# airmachine.net
KiCad netlist of a schematic drawn in Altium Designer
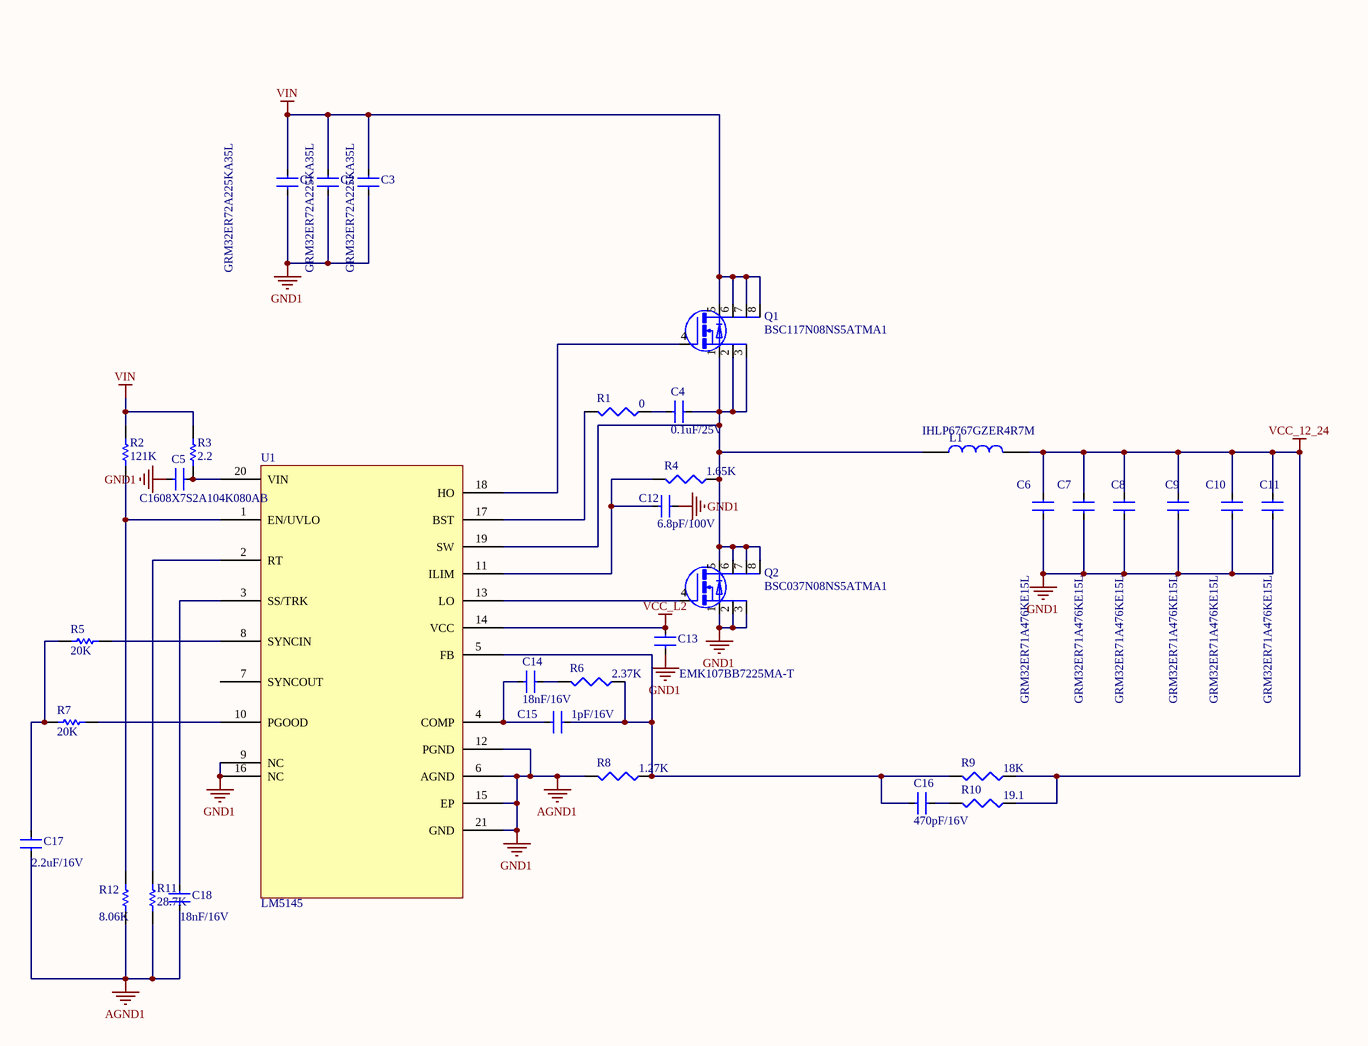
[diagram p0: airmachine.SchDoc]

(export (version "E")
  (design (tool "Eeschema 10.0.6"))
  (components
    (comp (ref "C1")
      (value "GRM32ER72A225KA35L")
      (footprint "1210C")
      (description "CCX85-103")
      (libsource (lib "无极性电容") (part "0.01UF"))
    )
    (comp (ref "C2")
      (value "GRM32ER72A225KA35L")
      (footprint "1210C")
      (description "CCX85-103")
      (libsource (lib "无极性电容") (part "0.01UF"))
    )
    (comp (ref "C3")
      (value "GRM32ER72A225KA35L")
      (footprint "1210C")
      (description "CCX85-103")
      (libsource (lib "无极性电容") (part "0.01UF"))
    )
    (comp (ref "C4")
      (value "0.1uF/25V")
      (footprint "0603C")
      (description "CCX85-103")
      (libsource (lib "无极性电容") (part "0.01UF"))
    )
    (comp (ref "C5")
      (value "C1608X7S2A104K080AB")
      (footprint "0603C")
      (description "CCX85-103")
      (libsource (lib "无极性电容") (part "0.01UF"))
    )
    (comp (ref "C6")
      (value "GRM32ER71A476KE15L")
      (footprint "1210C")
      (description "CCX85-103")
      (libsource (lib "无极性电容") (part "0.01UF"))
    )
    (comp (ref "C7")
      (value "GRM32ER71A476KE15L")
      (footprint "1210C")
      (description "CCX85-103")
      (libsource (lib "无极性电容") (part "0.01UF"))
    )
    (comp (ref "C8")
      (value "GRM32ER71A476KE15L")
      (footprint "1210C")
      (description "CCX85-103")
      (libsource (lib "无极性电容") (part "0.01UF"))
    )
    (comp (ref "C9")
      (value "GRM32ER71A476KE15L")
      (footprint "1210C")
      (description "CCX85-103")
      (libsource (lib "无极性电容") (part "0.01UF"))
    )
    (comp (ref "C10")
      (value "GRM32ER71A476KE15L")
      (footprint "1210C")
      (description "CCX85-103")
      (libsource (lib "无极性电容") (part "0.01UF"))
    )
    (comp (ref "C11")
      (value "GRM32ER71A476KE15L")
      (footprint "1210C")
      (description "CCX85-103")
      (libsource (lib "无极性电容") (part "0.01UF"))
    )
    (comp (ref "C12")
      (value "6.8pF/100V")
      (footprint "0603C")
      (description "CCX85-103")
      (libsource (lib "无极性电容") (part "0.01UF"))
    )
    (comp (ref "C13")
      (value "EMK107BB7225MA-T")
      (footprint "0603C")
      (description "CCX85-103")
      (libsource (lib "无极性电容") (part "0.01UF"))
    )
    (comp (ref "C14")
      (value "18nF/16V")
      (footprint "0603C")
      (description "CCX85-103")
      (libsource (lib "无极性电容") (part "0.01UF"))
    )
    (comp (ref "C15")
      (value "1pF/16V")
      (footprint "0603C")
      (description "CCX85-103")
      (libsource (lib "无极性电容") (part "0.01UF"))
    )
    (comp (ref "C16")
      (value "470pF/16V")
      (footprint "0603C")
      (description "CCX85-103")
      (libsource (lib "无极性电容") (part "0.01UF"))
    )
    (comp (ref "C17")
      (value "2.2uF/16V")
      (footprint "0603C")
      (description "CCX85-103")
      (libsource (lib "无极性电容") (part "0.01UF"))
    )
    (comp (ref "C18")
      (value "18nF/16V")
      (footprint "0603C")
      (description "CCX85-103")
      (libsource (lib "无极性电容") (part "0.01UF"))
    )
    (comp (ref "L1")
      (value "IHLP6767GZER4R7M")
      (footprint "IHLP-6767GZ")
      (libsource (lib "*") (part "INDUCTOR"))
    )
    (comp (ref "Q1")
      (value "BSC117N08NS5ATMA1")
      (footprint "PowerPAK SO-8")
      (description "Si4004DY")
      (libsource (lib "Schlib_20110825") (part "Si4004DY"))
    )
    (comp (ref "Q2")
      (value "BSC037N08NS5ATMA1")
      (footprint "PowerPAK SO-8")
      (description "Si4004DY")
      (libsource (lib "Schlib_20110825") (part "Si4004DY"))
    )
    (comp (ref "R1")
      (value "0")
      (footprint "0603R")
      (description "Resistor")
      (fields (field (name "PUBLISHER") "Altium Limited"))
      (libsource (lib "SM") (part "Res3"))
    )
    (comp (ref "R2")
      (value "121K")
      (footprint "0805R")
      (description "Semiconductor Resistor")
      (fields (field (name "PUBLISHER") "Altium Limited"))
      (libsource (lib "Miscellaneous Devices") (part "Res Semi"))
    )
    (comp (ref "R3")
      (value "2.2")
      (footprint "0603R")
      (description "Semiconductor Resistor")
      (fields (field (name "PUBLISHER") "Altium Limited"))
      (libsource (lib "Miscellaneous Devices") (part "Res Semi"))
    )
    (comp (ref "R4")
      (value "1.65K")
      (footprint "0603R")
      (description "Resistor")
      (fields (field (name "PUBLISHER") "Altium Limited"))
      (libsource (lib "SM") (part "Res3"))
    )
    (comp (ref "R5")
      (value "20K")
      (footprint "0603R")
      (description "Semiconductor Resistor")
      (fields (field (name "PUBLISHER") "Altium Limited"))
      (libsource (lib "Miscellaneous Devices") (part "Res Semi"))
    )
    (comp (ref "R6")
      (value "2.37K")
      (footprint "0603R")
      (description "Resistor")
      (fields (field (name "PUBLISHER") "Altium Limited"))
      (libsource (lib "SM") (part "Res3"))
    )
    (comp (ref "R7")
      (value "20K")
      (footprint "0603R")
      (description "Semiconductor Resistor")
      (fields (field (name "PUBLISHER") "Altium Limited"))
      (libsource (lib "Miscellaneous Devices") (part "Res Semi"))
    )
    (comp (ref "R8")
      (value "1.27K")
      (footprint "0603R")
      (description "Resistor")
      (fields (field (name "PUBLISHER") "Altium Limited"))
      (libsource (lib "SM") (part "Res3"))
    )
    (comp (ref "R9")
      (value "18K")
      (footprint "0603R")
      (description "Resistor")
      (fields (field (name "PUBLISHER") "Altium Limited"))
      (libsource (lib "SM") (part "Res3"))
    )
    (comp (ref "R10")
      (value "19.1")
      (footprint "0603R")
      (description "Resistor")
      (fields (field (name "PUBLISHER") "Altium Limited"))
      (libsource (lib "SM") (part "Res3"))
    )
    (comp (ref "R11")
      (value "28.7K")
      (footprint "0603R")
      (description "Semiconductor Resistor")
      (fields (field (name "PUBLISHER") "Altium Limited"))
      (libsource (lib "Miscellaneous Devices") (part "Res Semi"))
    )
    (comp (ref "R12")
      (value "8.06K")
      (footprint "0603R")
      (description "Semiconductor Resistor")
      (fields (field (name "PUBLISHER") "Altium Limited"))
      (libsource (lib "Miscellaneous Devices") (part "Res Semi"))
    )
    (comp (ref "U1")
      (value "LM5145")
      (footprint "QFN050P600-8N")
      (libsource (lib "Schlib_20110825") (part "LM5145"))
    )
  )
  (nets
    (net (code "1") (name "AGND1") (class "Default")
      (node (ref "C1") (pin "2") (pinfunction "2_2") (pintype "passive"))
      (node (ref "C10") (pin "2") (pinfunction "2_2") (pintype "passive"))
      (node (ref "C11") (pin "2") (pinfunction "2_2") (pintype "passive"))
      (node (ref "C12") (pin "1") (pinfunction "1_1") (pintype "passive"))
      (node (ref "C13") (pin "2") (pinfunction "2_2") (pintype "passive"))
      (node (ref "C17") (pin "2") (pinfunction "2_2") (pintype "passive"))
      (node (ref "C18") (pin "2") (pinfunction "2_2") (pintype "passive"))
      (node (ref "C2") (pin "2") (pinfunction "2_2") (pintype "passive"))
      (node (ref "C3") (pin "2") (pinfunction "2_2") (pintype "passive"))
      (node (ref "C5") (pin "1") (pinfunction "1_1") (pintype "passive"))
      (node (ref "C6") (pin "2") (pinfunction "2_2") (pintype "passive"))
      (node (ref "C7") (pin "2") (pinfunction "2_2") (pintype "passive"))
      (node (ref "C8") (pin "2") (pinfunction "2_2") (pintype "passive"))
      (node (ref "C9") (pin "2") (pinfunction "2_2") (pintype "passive"))
      (node (ref "Q2") (pin "1") (pinfunction "S_1") (pintype "passive"))
      (node (ref "Q2") (pin "2") (pinfunction "S_2") (pintype "passive"))
      (node (ref "Q2") (pin "3") (pinfunction "S_3") (pintype "passive"))
      (node (ref "R11") (pin "1") (pinfunction "1_1") (pintype "passive"))
      (node (ref "R12") (pin "1") (pinfunction "1_1") (pintype "passive"))
      (node (ref "R8") (pin "2") (pinfunction "2_2") (pintype "passive"))
      (node (ref "U1") (pin "12") (pinfunction "PGND_12") (pintype "passive"))
      (node (ref "U1") (pin "15") (pinfunction "EP_15") (pintype "passive"))
      (node (ref "U1") (pin "16") (pinfunction "NC_16") (pintype "passive"))
      (node (ref "U1") (pin "21") (pinfunction "GND_21") (pintype "passive"))
      (node (ref "U1") (pin "6") (pinfunction "AGND_6") (pintype "passive"))
      (node (ref "U1") (pin "9") (pinfunction "NC_9") (pintype "passive"))
    )
    (net (code "2") (name "Net-(C4-Pad1)") (class "Default")
      (node (ref "C4") (pin "1") (pinfunction "1_1") (pintype "passive"))
      (node (ref "R1") (pin "1") (pinfunction "1_1") (pintype "passive"))
    )
    (net (code "3") (name "Net-(C14-Pad2)") (class "Default")
      (node (ref "C14") (pin "2") (pinfunction "2_2") (pintype "passive"))
      (node (ref "R6") (pin "2") (pinfunction "2_2") (pintype "passive"))
    )
    (net (code "4") (name "Net-(C16-Pad2)") (class "Default")
      (node (ref "C16") (pin "2") (pinfunction "2_2") (pintype "passive"))
      (node (ref "R10") (pin "2") (pinfunction "2_2") (pintype "passive"))
    )
    (net (code "5") (name "Net-(C17-Pad1)") (class "Default")
      (node (ref "C17") (pin "1") (pinfunction "1_1") (pintype "passive"))
      (node (ref "R5") (pin "2") (pinfunction "2_2") (pintype "passive"))
      (node (ref "R7") (pin "2") (pinfunction "2_2") (pintype "passive"))
    )
    (net (code "6") (name "Net-(Q1-G)") (class "Default")
      (node (ref "Q1") (pin "4") (pinfunction "G_4") (pintype "passive"))
      (node (ref "U1") (pin "18") (pinfunction "HO_18") (pintype "passive"))
    )
    (net (code "7") (name "Net-(Q2-G)") (class "Default")
      (node (ref "Q2") (pin "4") (pinfunction "G_4") (pintype "passive"))
      (node (ref "U1") (pin "13") (pinfunction "LO_13") (pintype "passive"))
    )
    (net (code "8") (name "Net-(U1-BST)") (class "Default")
      (node (ref "R1") (pin "2") (pinfunction "2_2") (pintype "passive"))
      (node (ref "U1") (pin "17") (pinfunction "BST_17") (pintype "passive"))
    )
    (net (code "9") (name "Net-(U1-COMP)") (class "Default")
      (node (ref "C14") (pin "1") (pinfunction "1_1") (pintype "passive"))
      (node (ref "C15") (pin "1") (pinfunction "1_1") (pintype "passive"))
      (node (ref "U1") (pin "4") (pinfunction "COMP_4") (pintype "passive"))
    )
    (net (code "10") (name "Net-(U1-EN{slash}UVLO)") (class "Default")
      (node (ref "R12") (pin "2") (pinfunction "2_2") (pintype "passive"))
      (node (ref "R2") (pin "1") (pinfunction "1_1") (pintype "passive"))
      (node (ref "U1") (pin "1") (pinfunction "EN/UVLO_1") (pintype "passive"))
    )
    (net (code "11") (name "Net-(U1-FB)") (class "Default")
      (node (ref "C15") (pin "2") (pinfunction "2_2") (pintype "passive"))
      (node (ref "C16") (pin "1") (pinfunction "1_1") (pintype "passive"))
      (node (ref "R6") (pin "1") (pinfunction "1_1") (pintype "passive"))
      (node (ref "R8") (pin "1") (pinfunction "1_1") (pintype "passive"))
      (node (ref "R9") (pin "2") (pinfunction "2_2") (pintype "passive"))
      (node (ref "U1") (pin "5") (pinfunction "FB_5") (pintype "passive"))
    )
    (net (code "12") (name "Net-(U1-ILIM)") (class "Default")
      (node (ref "C12") (pin "2") (pinfunction "2_2") (pintype "passive"))
      (node (ref "R4") (pin "2") (pinfunction "2_2") (pintype "passive"))
      (node (ref "U1") (pin "11") (pinfunction "ILIM_11") (pintype "passive"))
    )
    (net (code "13") (name "Net-(U1-PGOOD)") (class "Default")
      (node (ref "R7") (pin "1") (pinfunction "1_1") (pintype "passive"))
      (node (ref "U1") (pin "10") (pinfunction "PGOOD_10") (pintype "passive"))
    )
    (net (code "14") (name "Net-(U1-RT)") (class "Default")
      (node (ref "R11") (pin "2") (pinfunction "2_2") (pintype "passive"))
      (node (ref "U1") (pin "2") (pinfunction "RT_2") (pintype "passive"))
    )
    (net (code "15") (name "Net-(U1-SS{slash}TRK)") (class "Default")
      (node (ref "C18") (pin "1") (pinfunction "1_1") (pintype "passive"))
      (node (ref "U1") (pin "3") (pinfunction "SS/TRK_3") (pintype "passive"))
    )
    (net (code "16") (name "Net-(U1-SW)") (class "Default")
      (node (ref "C4") (pin "2") (pinfunction "2_2") (pintype "passive"))
      (node (ref "L1") (pin "1") (pinfunction "1_1") (pintype "passive"))
      (node (ref "Q1") (pin "1") (pinfunction "S_1") (pintype "passive"))
      (node (ref "Q1") (pin "2") (pinfunction "S_2") (pintype "passive"))
      (node (ref "Q1") (pin "3") (pinfunction "S_3") (pintype "passive"))
      (node (ref "Q2") (pin "5") (pinfunction "D_5") (pintype "passive"))
      (node (ref "Q2") (pin "6") (pinfunction "D_6") (pintype "passive"))
      (node (ref "Q2") (pin "7") (pinfunction "D_7") (pintype "passive"))
      (node (ref "Q2") (pin "8") (pinfunction "D_8") (pintype "passive"))
      (node (ref "R4") (pin "1") (pinfunction "1_1") (pintype "passive"))
      (node (ref "U1") (pin "19") (pinfunction "SW_19") (pintype "passive"))
    )
    (net (code "17") (name "Net-(U1-SYNCIN)") (class "Default")
      (node (ref "R5") (pin "1") (pinfunction "1_1") (pintype "passive"))
      (node (ref "U1") (pin "8") (pinfunction "SYNCIN_8") (pintype "passive"))
    )
    (net (code "18") (name "Net-(U1-VIN)") (class "Default")
      (node (ref "C5") (pin "2") (pinfunction "2_2") (pintype "passive"))
      (node (ref "R3") (pin "2") (pinfunction "2_2") (pintype "passive"))
      (node (ref "U1") (pin "20") (pinfunction "VIN_20") (pintype "passive"))
    )
    (net (code "19") (name "VCC_12_24") (class "Default")
      (node (ref "C10") (pin "1") (pinfunction "1_1") (pintype "passive"))
      (node (ref "C11") (pin "1") (pinfunction "1_1") (pintype "passive"))
      (node (ref "C6") (pin "1") (pinfunction "1_1") (pintype "passive"))
      (node (ref "C7") (pin "1") (pinfunction "1_1") (pintype "passive"))
      (node (ref "C8") (pin "1") (pinfunction "1_1") (pintype "passive"))
      (node (ref "C9") (pin "1") (pinfunction "1_1") (pintype "passive"))
      (node (ref "L1") (pin "2") (pinfunction "2_2") (pintype "passive"))
      (node (ref "R10") (pin "1") (pinfunction "1_1") (pintype "passive"))
      (node (ref "R9") (pin "1") (pinfunction "1_1") (pintype "passive"))
    )
    (net (code "20") (name "VCC_L2") (class "Default")
      (node (ref "C13") (pin "1") (pinfunction "1_1") (pintype "passive"))
      (node (ref "U1") (pin "14") (pinfunction "VCC_14") (pintype "passive"))
    )
    (net (code "21") (name "VIN") (class "Default")
      (node (ref "C1") (pin "1") (pinfunction "1_1") (pintype "passive"))
      (node (ref "C2") (pin "1") (pinfunction "1_1") (pintype "passive"))
      (node (ref "C3") (pin "1") (pinfunction "1_1") (pintype "passive"))
      (node (ref "Q1") (pin "5") (pinfunction "D_5") (pintype "passive"))
      (node (ref "Q1") (pin "6") (pinfunction "D_6") (pintype "passive"))
      (node (ref "Q1") (pin "7") (pinfunction "D_7") (pintype "passive"))
      (node (ref "Q1") (pin "8") (pinfunction "D_8") (pintype "passive"))
      (node (ref "R2") (pin "2") (pinfunction "2_2") (pintype "passive"))
      (node (ref "R3") (pin "1") (pinfunction "1_1") (pintype "passive"))
    )
    (net (code "22") (name "unconnected-(U1-SYNCOUT-Pad7)") (class "Default")
      (node (ref "U1") (pin "7") (pinfunction "SYNCOUT_7") (pintype "passive"))
    )
  )
)
